# STM32G473RETx_LQFP64_MCU.net
KiCad netlist of a schematic drawn in Altium Designer
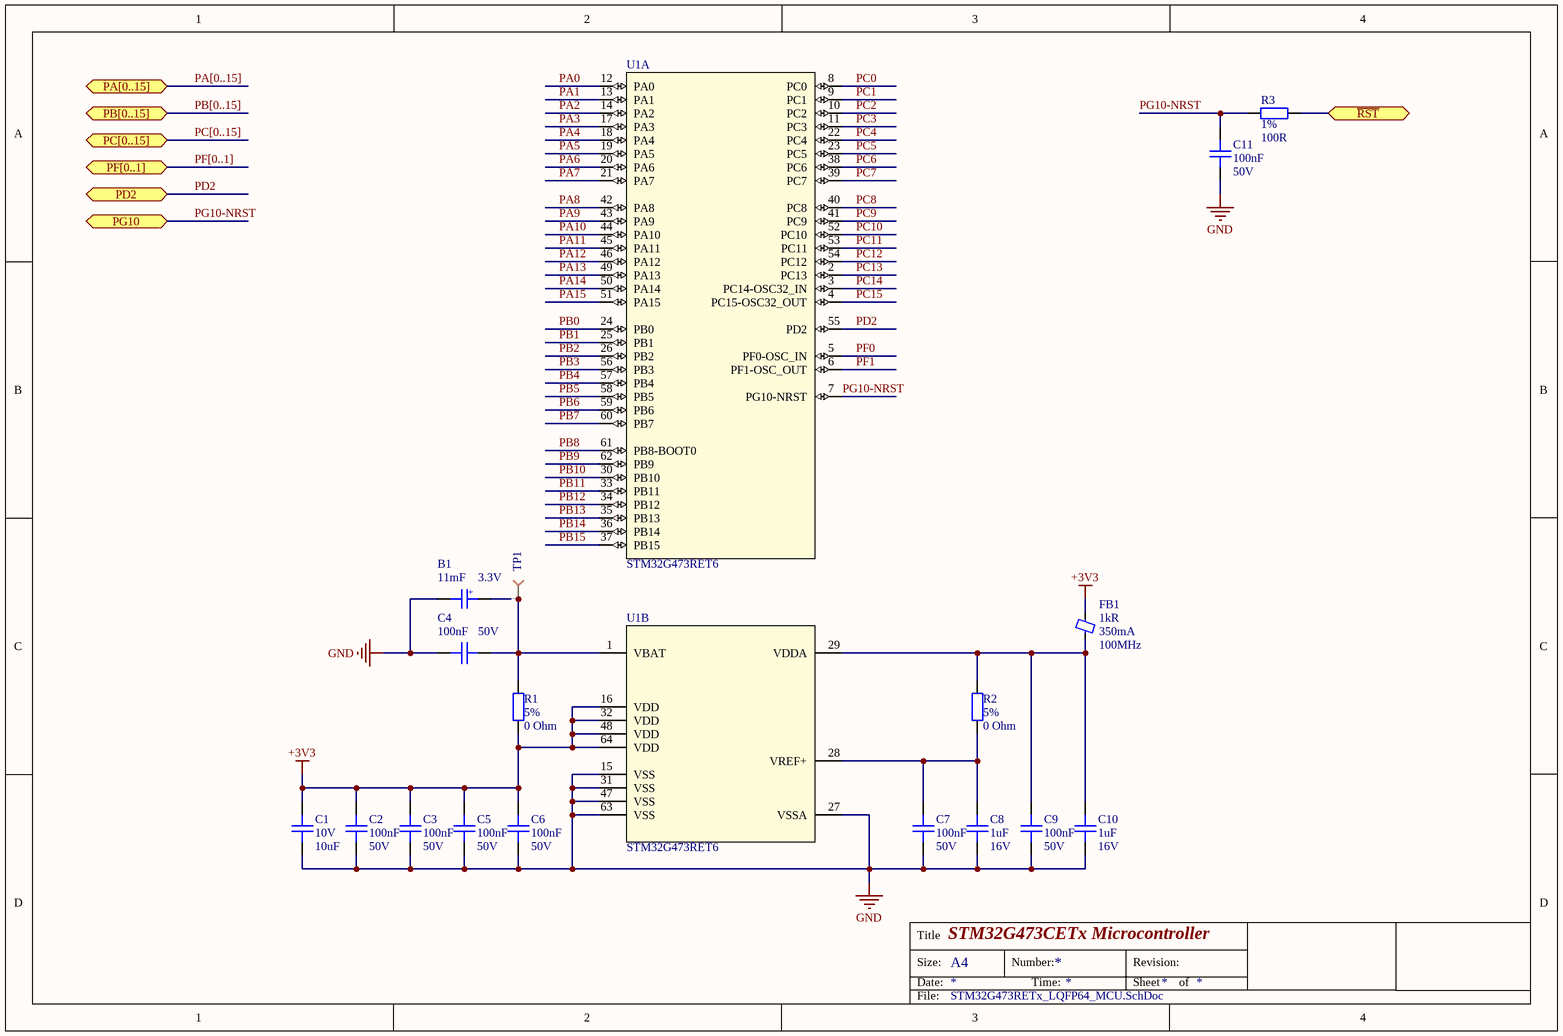
[diagram p0: STM32G473RETx_LQFP64_MCU.SchDoc]

(export (version "E")
  (design (tool "Eeschema 10.0.6"))
  (components
    (comp (ref "B1")
      (value "CAP 11MF 3.3V SURFACE MNT")
      (footprint "CAPCP3225X100N")
      (description "11mF (EDLC) Supercapacitor 3.3V 1210 (3225 Metric)")
      (fields
        (field (name "MANUFACTURER") "Seiko")
        (field (name "MANUFACTURER PART NUMBER") "CPH3225A")
        (field (name "CAPACITANCE") "11mF")
        (field (name "VOLTAGE RATING") "3.3V")
      )
      (libsource (lib "BLDC_Motor_Driver") (part "CAP 11MF 3.3V SURFACE MNT"))
    )
    (comp (ref "C1")
      (value "CAP CER 10uF X7R 10% 0805")
      (footprint "C0805")
      (description "Capacitor,10uF,10V,X7R,10%,0805,Murata")
      (fields
        (field (name "MANUFACTURER") "Murata")
        (field (name "MANUFACTURER PART NUMBER") "GRM21BR71A106KA73L")
        (field (name "VOLTAGE RATING") "10V")
        (field (name "CAPACITANCE") "10uF")
      )
      (libsource (lib "capacitors_smd") (part "CAP CER 10uF X7R 10% 0805"))
    )
    (comp (ref "C2")
      (value "CAP CER 0.1UF 50V X7R 0402")
      (footprint "C0402")
      (description "0.1µF ±10% 50V Ceramic Capacitor X7R 0402 (1005 Metric)")
      (fields
        (field (name "MANUFACTURER") "TDK")
        (field (name "MANUFACTURER PART NUMBER") "CGA2B3X7R1H104K050BB")
        (field (name "CAPACITANCE") "100nF")
        (field (name "VOLTAGE") "50V")
      )
      (libsource (lib "capacitors_smd") (part "CAP CER 0.1UF 50V X7R 0402"))
    )
    (comp (ref "C3")
      (value "CAP CER 0.1UF 50V X7R 0402")
      (footprint "C0402")
      (description "0.1µF ±10% 50V Ceramic Capacitor X7R 0402 (1005 Metric)")
      (fields
        (field (name "MANUFACTURER") "TDK")
        (field (name "MANUFACTURER PART NUMBER") "CGA2B3X7R1H104K050BB")
        (field (name "CAPACITANCE") "100nF")
        (field (name "VOLTAGE") "50V")
      )
      (libsource (lib "capacitors_smd") (part "CAP CER 0.1UF 50V X7R 0402"))
    )
    (comp (ref "C4")
      (value "CAP CER 0.1UF 50V X7R 0402")
      (footprint "C0402")
      (description "0.1µF ±10% 50V Ceramic Capacitor X7R 0402 (1005 Metric)")
      (fields
        (field (name "MANUFACTURER") "TDK")
        (field (name "MANUFACTURER PART NUMBER") "CGA2B3X7R1H104K050BB")
        (field (name "CAPACITANCE") "100nF")
        (field (name "VOLTAGE") "50V")
      )
      (libsource (lib "capacitors_smd") (part "CAP CER 0.1UF 50V X7R 0402"))
    )
    (comp (ref "C5")
      (value "CAP CER 0.1UF 50V X7R 0402")
      (footprint "C0402")
      (description "0.1µF ±10% 50V Ceramic Capacitor X7R 0402 (1005 Metric)")
      (fields
        (field (name "MANUFACTURER") "TDK")
        (field (name "MANUFACTURER PART NUMBER") "CGA2B3X7R1H104K050BB")
        (field (name "CAPACITANCE") "100nF")
        (field (name "VOLTAGE") "50V")
      )
      (libsource (lib "capacitors_smd") (part "CAP CER 0.1UF 50V X7R 0402"))
    )
    (comp (ref "C6")
      (value "CAP CER 0.1UF 50V X7R 0402")
      (footprint "C0402")
      (description "0.1µF ±10% 50V Ceramic Capacitor X7R 0402 (1005 Metric)")
      (fields
        (field (name "MANUFACTURER") "TDK")
        (field (name "MANUFACTURER PART NUMBER") "CGA2B3X7R1H104K050BB")
        (field (name "CAPACITANCE") "100nF")
        (field (name "VOLTAGE") "50V")
      )
      (libsource (lib "capacitors_smd") (part "CAP CER 0.1UF 50V X7R 0402"))
    )
    (comp (ref "C7")
      (value "CAP CER 0.1UF 50V X7R 0402")
      (footprint "C0402")
      (description "0.1µF ±10% 50V Ceramic Capacitor X7R 0402 (1005 Metric)")
      (fields
        (field (name "MANUFACTURER") "TDK")
        (field (name "MANUFACTURER PART NUMBER") "CGA2B3X7R1H104K050BB")
        (field (name "CAPACITANCE") "100nF")
        (field (name "VOLTAGE") "50V")
      )
      (libsource (lib "capacitors_smd") (part "CAP CER 0.1UF 50V X7R 0402"))
    )
    (comp (ref "C8")
      (value "CAP CER 1UF 16V X5R 0402")
      (footprint "C0402")
      (description "1µF ±10% 16V Ceramic Capacitor X5R 0402 (1005 Metric)")
      (fields
        (field (name "MANUFACTURER") "Yageo")
        (field (name "MANUFACTURER PART NUMBER") "CC0402KRX5R7BB105")
        (field (name "CAPACITANCE") "1uF")
        (field (name "VOLTAGE RATING") "16V")
      )
      (libsource (lib "capacitors_smd") (part "CAP CER 1UF 16V X5R 0402"))
    )
    (comp (ref "C9")
      (value "CAP CER 0.1UF 50V X7R 0402")
      (footprint "C0402")
      (description "0.1µF ±10% 50V Ceramic Capacitor X7R 0402 (1005 Metric)")
      (fields
        (field (name "MANUFACTURER") "TDK")
        (field (name "MANUFACTURER PART NUMBER") "CGA2B3X7R1H104K050BB")
        (field (name "CAPACITANCE") "100nF")
        (field (name "VOLTAGE") "50V")
      )
      (libsource (lib "capacitors_smd") (part "CAP CER 0.1UF 50V X7R 0402"))
    )
    (comp (ref "C10")
      (value "CAP CER 1UF 16V X5R 0402")
      (footprint "C0402")
      (description "1µF ±10% 16V Ceramic Capacitor X5R 0402 (1005 Metric)")
      (fields
        (field (name "MANUFACTURER") "Yageo")
        (field (name "MANUFACTURER PART NUMBER") "CC0402KRX5R7BB105")
        (field (name "CAPACITANCE") "1uF")
        (field (name "VOLTAGE RATING") "16V")
      )
      (libsource (lib "capacitors_smd") (part "CAP CER 1UF 16V X5R 0402"))
    )
    (comp (ref "C11")
      (value "CAP CER 0.1UF 50V X7R 0402")
      (footprint "C0402")
      (description "0.1µF ±10% 50V Ceramic Capacitor X7R 0402 (1005 Metric)")
      (fields
        (field (name "MANUFACTURER") "TDK")
        (field (name "MANUFACTURER PART NUMBER") "CGA2B3X7R1H104K050BB")
        (field (name "CAPACITANCE") "100nF")
        (field (name "VOLTAGE") "50V")
      )
      (libsource (lib "capacitors_smd") (part "CAP CER 0.1UF 50V X7R 0402"))
    )
    (comp (ref "FB1")
      (value "FERRITE BEAD 1 KOHM 0402 1LN")
      (footprint "L0402")
      (description "1 kOhms @ 100MHz 1  Ferrite Bead 0402 (1005 Metric) 350mA 490mOhm")
      (fields
        (field (name "MANUFACTURER") "Murata")
        (field (name "MANUFACTURER PART NUMBER") "BLM15AX102SN1D")
        (field (name "IMPEDANCE") "1kR")
        (field (name "MAX DC CURRENT") "350mA")
        (field (name "TEST FREQUENCY") "100MHz")
      )
      (libsource (lib "ferrite_beads") (part "FERRITE BEAD 1 KOHM 0402 1LN"))
    )
    (comp (ref "R1")
      (value "RES SMD 0 OHM JUMPER 1/16W 0402")
      (footprint "R0402")
      (description "0 Ohms Jumper 0.063W, 1/16W Chip Resistor 0402 (1005 Metric) Moisture Resistant Thick Film")
      (fields
        (field (name "MANUFACTURER") "Yageo")
        (field (name "MANUFACTURER PART NUMBER") "RC0402JR-070RL")
        (field (name "TOLERANCE") "5%")
        (field (name "RESISTANCE") "0 Ohm")
      )
      (libsource (lib "resistors_smd") (part "RES SMD 0 OHM JUMPER 1/16W 0402"))
    )
    (comp (ref "R2")
      (value "RES SMD 0 OHM JUMPER 1/16W 0402")
      (footprint "R0402")
      (description "0 Ohms Jumper 0.063W, 1/16W Chip Resistor 0402 (1005 Metric) Moisture Resistant Thick Film")
      (fields
        (field (name "MANUFACTURER") "Yageo")
        (field (name "MANUFACTURER PART NUMBER") "RC0402JR-070RL")
        (field (name "TOLERANCE") "5%")
        (field (name "RESISTANCE") "0 Ohm")
      )
      (libsource (lib "resistors_smd") (part "RES SMD 0 OHM JUMPER 1/16W 0402"))
    )
    (comp (ref "R3")
      (value "RES SMD 100 OHM 1% 1/16W 0402")
      (footprint "R0402")
      (description "100 Ohms ±1% 0.063W, 1/16W Chip Resistor 0402 (1005 Metric) Moisture Resistant Thick Film")
      (fields
        (field (name "MANUFACTURER") "Yageo")
        (field (name "MANUFACTURER PART NUMBER") "RC0402FR-07100RL")
        (field (name "TOLERANCE") "1%")
        (field (name "RESISTANCE") "100R")
      )
      (libsource (lib "resistors_smd") (part "RES SMD 100 OHM 1% 1/16W 0402"))
    )
    (comp (ref "TP1")
      (value "Test Point Pad")
      (footprint "Testpoint")
      (description "Test Point. There is nothing to buy or mount.")
      (libsource (lib "BLDC_Motor_Driver") (part "Test Point Pad"))
    )
    (comp (ref "U1")
      (value "STM32G473RET6")
      (footprint "LQFP64-10x10mm")
      (description "ARM® Cortex®-M4 STM32G4 Microcontroller IC 32-Bit 170MHz 512KB (512K x 8) FLASH 64-LQFP (10x10)")
      (fields (field (name "MANUFACTURER") "STMicroelectronics"))
      (libsource (lib "BLDC_Motor_Driver") (part "IC STM32G473RETx LQFP64"))
    )
  )
  (nets
    (net (code "1") (name "+3V3") (class "Default")
      (node (ref "C1") (pin "1") (pinfunction "1_1") (pintype "passive"))
      (node (ref "C2") (pin "1") (pinfunction "1_1") (pintype "passive"))
      (node (ref "C3") (pin "1") (pinfunction "1_1") (pintype "passive"))
      (node (ref "C5") (pin "1") (pinfunction "1_1") (pintype "passive"))
      (node (ref "C6") (pin "1") (pinfunction "1_1") (pintype "passive"))
      (node (ref "FB1") (pin "2") (pinfunction "2_2") (pintype "passive"))
      (node (ref "R1") (pin "1") (pinfunction "1_1") (pintype "passive"))
      (node (ref "U1") (pin "16") (pinfunction "VDD_16") (pintype "power_in"))
      (node (ref "U1") (pin "32") (pinfunction "VDD_32") (pintype "power_in"))
      (node (ref "U1") (pin "48") (pinfunction "VDD_48") (pintype "power_in"))
      (node (ref "U1") (pin "64") (pinfunction "VDD_64") (pintype "power_in"))
    )
    (net (code "2") (name "/PA0") (class "Default")
      (node (ref "U1") (pin "12") (pinfunction "PA0_12") (pintype "bidirectional"))
    )
    (net (code "3") (name "/PA1") (class "Default")
      (node (ref "U1") (pin "13") (pinfunction "PA1_13") (pintype "bidirectional"))
    )
    (net (code "4") (name "/PA2") (class "Default")
      (node (ref "U1") (pin "14") (pinfunction "PA2_14") (pintype "bidirectional"))
    )
    (net (code "5") (name "/PA3") (class "Default")
      (node (ref "U1") (pin "17") (pinfunction "PA3_17") (pintype "bidirectional"))
    )
    (net (code "6") (name "/PA4") (class "Default")
      (node (ref "U1") (pin "18") (pinfunction "PA4_18") (pintype "bidirectional"))
    )
    (net (code "7") (name "/PA5") (class "Default")
      (node (ref "U1") (pin "19") (pinfunction "PA5_19") (pintype "bidirectional"))
    )
    (net (code "8") (name "/PA6") (class "Default")
      (node (ref "U1") (pin "20") (pinfunction "PA6_20") (pintype "bidirectional"))
    )
    (net (code "9") (name "/PA7") (class "Default")
      (node (ref "U1") (pin "21") (pinfunction "PA7_21") (pintype "bidirectional"))
    )
    (net (code "10") (name "/PA8") (class "Default")
      (node (ref "U1") (pin "42") (pinfunction "PA8_42") (pintype "bidirectional"))
    )
    (net (code "11") (name "/PA9") (class "Default")
      (node (ref "U1") (pin "43") (pinfunction "PA9_43") (pintype "bidirectional"))
    )
    (net (code "12") (name "/PA10") (class "Default")
      (node (ref "U1") (pin "44") (pinfunction "PA10_44") (pintype "bidirectional"))
    )
    (net (code "13") (name "/PA11") (class "Default")
      (node (ref "U1") (pin "45") (pinfunction "PA11_45") (pintype "bidirectional"))
    )
    (net (code "14") (name "/PA12") (class "Default")
      (node (ref "U1") (pin "46") (pinfunction "PA12_46") (pintype "bidirectional"))
    )
    (net (code "15") (name "/PA13") (class "Default")
      (node (ref "U1") (pin "49") (pinfunction "PA13_49") (pintype "bidirectional"))
    )
    (net (code "16") (name "/PA14") (class "Default")
      (node (ref "U1") (pin "50") (pinfunction "PA14_50") (pintype "bidirectional"))
    )
    (net (code "17") (name "/PA15") (class "Default")
      (node (ref "U1") (pin "51") (pinfunction "PA15_51") (pintype "bidirectional"))
    )
    (net (code "19") (name "/PB0") (class "Default")
      (node (ref "U1") (pin "24") (pinfunction "PB0_24") (pintype "bidirectional"))
    )
    (net (code "20") (name "/PB1") (class "Default")
      (node (ref "U1") (pin "25") (pinfunction "PB1_25") (pintype "bidirectional"))
    )
    (net (code "21") (name "/PB2") (class "Default")
      (node (ref "U1") (pin "26") (pinfunction "PB2_26") (pintype "bidirectional"))
    )
    (net (code "22") (name "/PB3") (class "Default")
      (node (ref "U1") (pin "56") (pinfunction "PB3_56") (pintype "bidirectional"))
    )
    (net (code "23") (name "/PB4") (class "Default")
      (node (ref "U1") (pin "57") (pinfunction "PB4_57") (pintype "bidirectional"))
    )
    (net (code "24") (name "/PB5") (class "Default")
      (node (ref "U1") (pin "58") (pinfunction "PB5_58") (pintype "bidirectional"))
    )
    (net (code "25") (name "/PB6") (class "Default")
      (node (ref "U1") (pin "59") (pinfunction "PB6_59") (pintype "bidirectional"))
    )
    (net (code "26") (name "/PB7") (class "Default")
      (node (ref "U1") (pin "60") (pinfunction "PB7_60") (pintype "bidirectional"))
    )
    (net (code "27") (name "/PB8") (class "Default")
      (node (ref "U1") (pin "61") (pinfunction "PB8-BOOT0_61") (pintype "bidirectional"))
    )
    (net (code "28") (name "/PB9") (class "Default")
      (node (ref "U1") (pin "62") (pinfunction "PB9_62") (pintype "bidirectional"))
    )
    (net (code "29") (name "/PB10") (class "Default")
      (node (ref "U1") (pin "30") (pinfunction "PB10_30") (pintype "bidirectional"))
    )
    (net (code "30") (name "/PB11") (class "Default")
      (node (ref "U1") (pin "33") (pinfunction "PB11_33") (pintype "bidirectional"))
    )
    (net (code "31") (name "/PB12") (class "Default")
      (node (ref "U1") (pin "34") (pinfunction "PB12_34") (pintype "bidirectional"))
    )
    (net (code "32") (name "/PB13") (class "Default")
      (node (ref "U1") (pin "35") (pinfunction "PB13_35") (pintype "bidirectional"))
    )
    (net (code "33") (name "/PB14") (class "Default")
      (node (ref "U1") (pin "36") (pinfunction "PB14_36") (pintype "bidirectional"))
    )
    (net (code "34") (name "/PB15") (class "Default")
      (node (ref "U1") (pin "37") (pinfunction "PB15_37") (pintype "bidirectional"))
    )
    (net (code "36") (name "/PC0") (class "Default")
      (node (ref "U1") (pin "8") (pinfunction "PC0_8") (pintype "bidirectional"))
    )
    (net (code "37") (name "/PC1") (class "Default")
      (node (ref "U1") (pin "9") (pinfunction "PC1_9") (pintype "bidirectional"))
    )
    (net (code "38") (name "/PC2") (class "Default")
      (node (ref "U1") (pin "10") (pinfunction "PC2_10") (pintype "bidirectional"))
    )
    (net (code "39") (name "/PC3") (class "Default")
      (node (ref "U1") (pin "11") (pinfunction "PC3_11") (pintype "bidirectional"))
    )
    (net (code "40") (name "/PC4") (class "Default")
      (node (ref "U1") (pin "22") (pinfunction "PC4_22") (pintype "bidirectional"))
    )
    (net (code "41") (name "/PC5") (class "Default")
      (node (ref "U1") (pin "23") (pinfunction "PC5_23") (pintype "bidirectional"))
    )
    (net (code "42") (name "/PC6") (class "Default")
      (node (ref "U1") (pin "38") (pinfunction "PC6_38") (pintype "bidirectional"))
    )
    (net (code "43") (name "/PC7") (class "Default")
      (node (ref "U1") (pin "39") (pinfunction "PC7_39") (pintype "bidirectional"))
    )
    (net (code "44") (name "/PC8") (class "Default")
      (node (ref "U1") (pin "40") (pinfunction "PC8_40") (pintype "bidirectional"))
    )
    (net (code "45") (name "/PC9") (class "Default")
      (node (ref "U1") (pin "41") (pinfunction "PC9_41") (pintype "bidirectional"))
    )
    (net (code "46") (name "/PC10") (class "Default")
      (node (ref "U1") (pin "52") (pinfunction "PC10_52") (pintype "bidirectional"))
    )
    (net (code "47") (name "/PC11") (class "Default")
      (node (ref "U1") (pin "53") (pinfunction "PC11_53") (pintype "bidirectional"))
    )
    (net (code "48") (name "/PC12") (class "Default")
      (node (ref "U1") (pin "54") (pinfunction "PC12_54") (pintype "bidirectional"))
    )
    (net (code "49") (name "/PC13") (class "Default")
      (node (ref "U1") (pin "2") (pinfunction "PC13_2") (pintype "bidirectional"))
    )
    (net (code "50") (name "/PC14") (class "Default")
      (node (ref "U1") (pin "3") (pinfunction "PC14-OSC32_IN_3") (pintype "bidirectional"))
    )
    (net (code "51") (name "/PC15") (class "Default")
      (node (ref "U1") (pin "4") (pinfunction "PC15-OSC32_OUT_4") (pintype "bidirectional"))
    )
    (net (code "53") (name "/PD2") (class "Default")
      (node (ref "U1") (pin "55") (pinfunction "PD2_55") (pintype "bidirectional"))
    )
    (net (code "54") (name "/PF0") (class "Default")
      (node (ref "U1") (pin "5") (pinfunction "PF0-OSC_IN_5") (pintype "bidirectional"))
    )
    (net (code "55") (name "/PF1") (class "Default")
      (node (ref "U1") (pin "6") (pinfunction "PF1-OSC_OUT_6") (pintype "bidirectional"))
    )
    (net (code "57") (name "/PG10-NRST") (class "Default")
      (node (ref "C11") (pin "1") (pinfunction "1_1") (pintype "passive"))
      (node (ref "R3") (pin "2") (pinfunction "2_2") (pintype "passive"))
      (node (ref "U1") (pin "7") (pinfunction "PG10-NRST_7") (pintype "bidirectional"))
    )
    (net (code "58") (name "/RST") (class "Default")
      (node (ref "R3") (pin "1") (pinfunction "1_1") (pintype "passive"))
    )
    (net (code "59") (name "GND") (class "Default")
      (node (ref "B1") (pin "2") (pinfunction "2_2") (pintype "passive"))
      (node (ref "C1") (pin "2") (pinfunction "2_2") (pintype "passive"))
      (node (ref "C10") (pin "1") (pinfunction "1_1") (pintype "passive"))
      (node (ref "C11") (pin "2") (pinfunction "2_2") (pintype "passive"))
      (node (ref "C2") (pin "2") (pinfunction "2_2") (pintype "passive"))
      (node (ref "C3") (pin "2") (pinfunction "2_2") (pintype "passive"))
      (node (ref "C4") (pin "2") (pinfunction "2_2") (pintype "passive"))
      (node (ref "C5") (pin "2") (pinfunction "2_2") (pintype "passive"))
      (node (ref "C6") (pin "2") (pinfunction "2_2") (pintype "passive"))
      (node (ref "C7") (pin "1") (pinfunction "1_1") (pintype "passive"))
      (node (ref "C8") (pin "1") (pinfunction "1_1") (pintype "passive"))
      (node (ref "C9") (pin "1") (pinfunction "1_1") (pintype "passive"))
      (node (ref "U1") (pin "15") (pinfunction "VSS_15") (pintype "power_in"))
      (node (ref "U1") (pin "27") (pinfunction "VSSA_27") (pintype "power_in"))
      (node (ref "U1") (pin "31") (pinfunction "VSS_31") (pintype "power_in"))
      (node (ref "U1") (pin "47") (pinfunction "VSS_47") (pintype "power_in"))
      (node (ref "U1") (pin "63") (pinfunction "VSS_63") (pintype "power_in"))
    )
    (net (code "60") (name "Net-(U1B-VBAT)") (class "Default")
      (node (ref "B1") (pin "1") (pinfunction "1_1") (pintype "passive"))
      (node (ref "C4") (pin "1") (pinfunction "1_1") (pintype "passive"))
      (node (ref "R1") (pin "2") (pinfunction "2_2") (pintype "passive"))
      (node (ref "TP1") (pin "1") (pinfunction "1_1") (pintype "passive"))
      (node (ref "U1") (pin "1") (pinfunction "VBAT_1") (pintype "power_in"))
    )
    (net (code "61") (name "Net-(U1B-VDDA)") (class "Default")
      (node (ref "C10") (pin "2") (pinfunction "2_2") (pintype "passive"))
      (node (ref "C9") (pin "2") (pinfunction "2_2") (pintype "passive"))
      (node (ref "FB1") (pin "1") (pinfunction "1_1") (pintype "passive"))
      (node (ref "R2") (pin "2") (pinfunction "2_2") (pintype "passive"))
      (node (ref "U1") (pin "29") (pinfunction "VDDA_29") (pintype "power_in"))
    )
    (net (code "62") (name "Net-(U1B-VREF+)") (class "Default")
      (node (ref "C7") (pin "2") (pinfunction "2_2") (pintype "passive"))
      (node (ref "C8") (pin "2") (pinfunction "2_2") (pintype "passive"))
      (node (ref "R2") (pin "1") (pinfunction "1_1") (pintype "passive"))
      (node (ref "U1") (pin "28") (pinfunction "VREF+_28") (pintype "power_in"))
    )
  )
)
